# SMC_FrontPanel_ExtensionBoard_V14_5.net
KiCad netlist of a schematic drawn in EAGLE
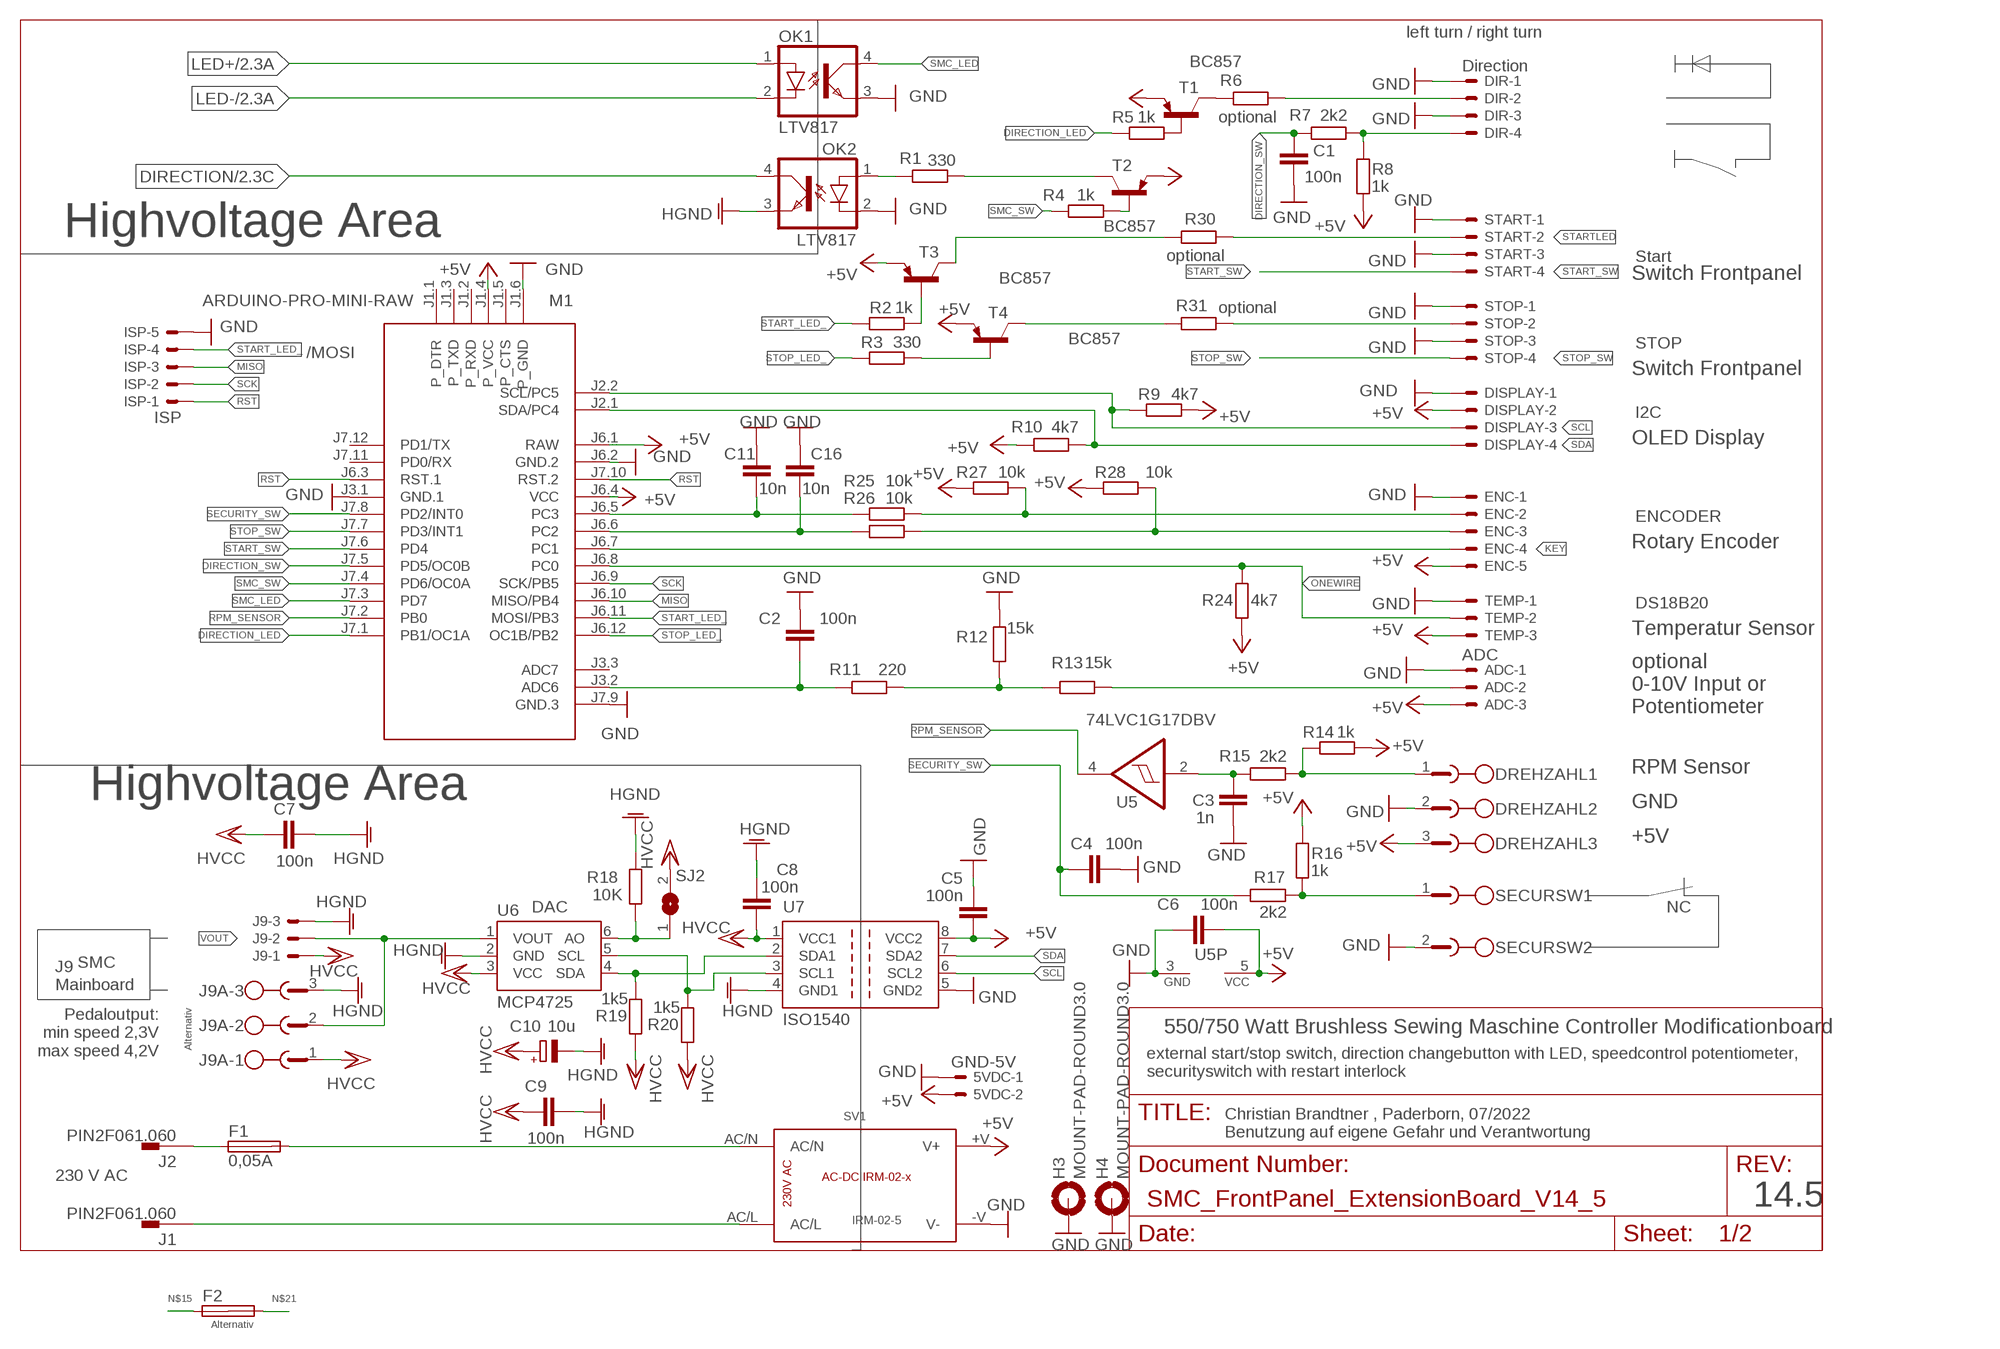
[diagram p0: schematic, sheet 1]
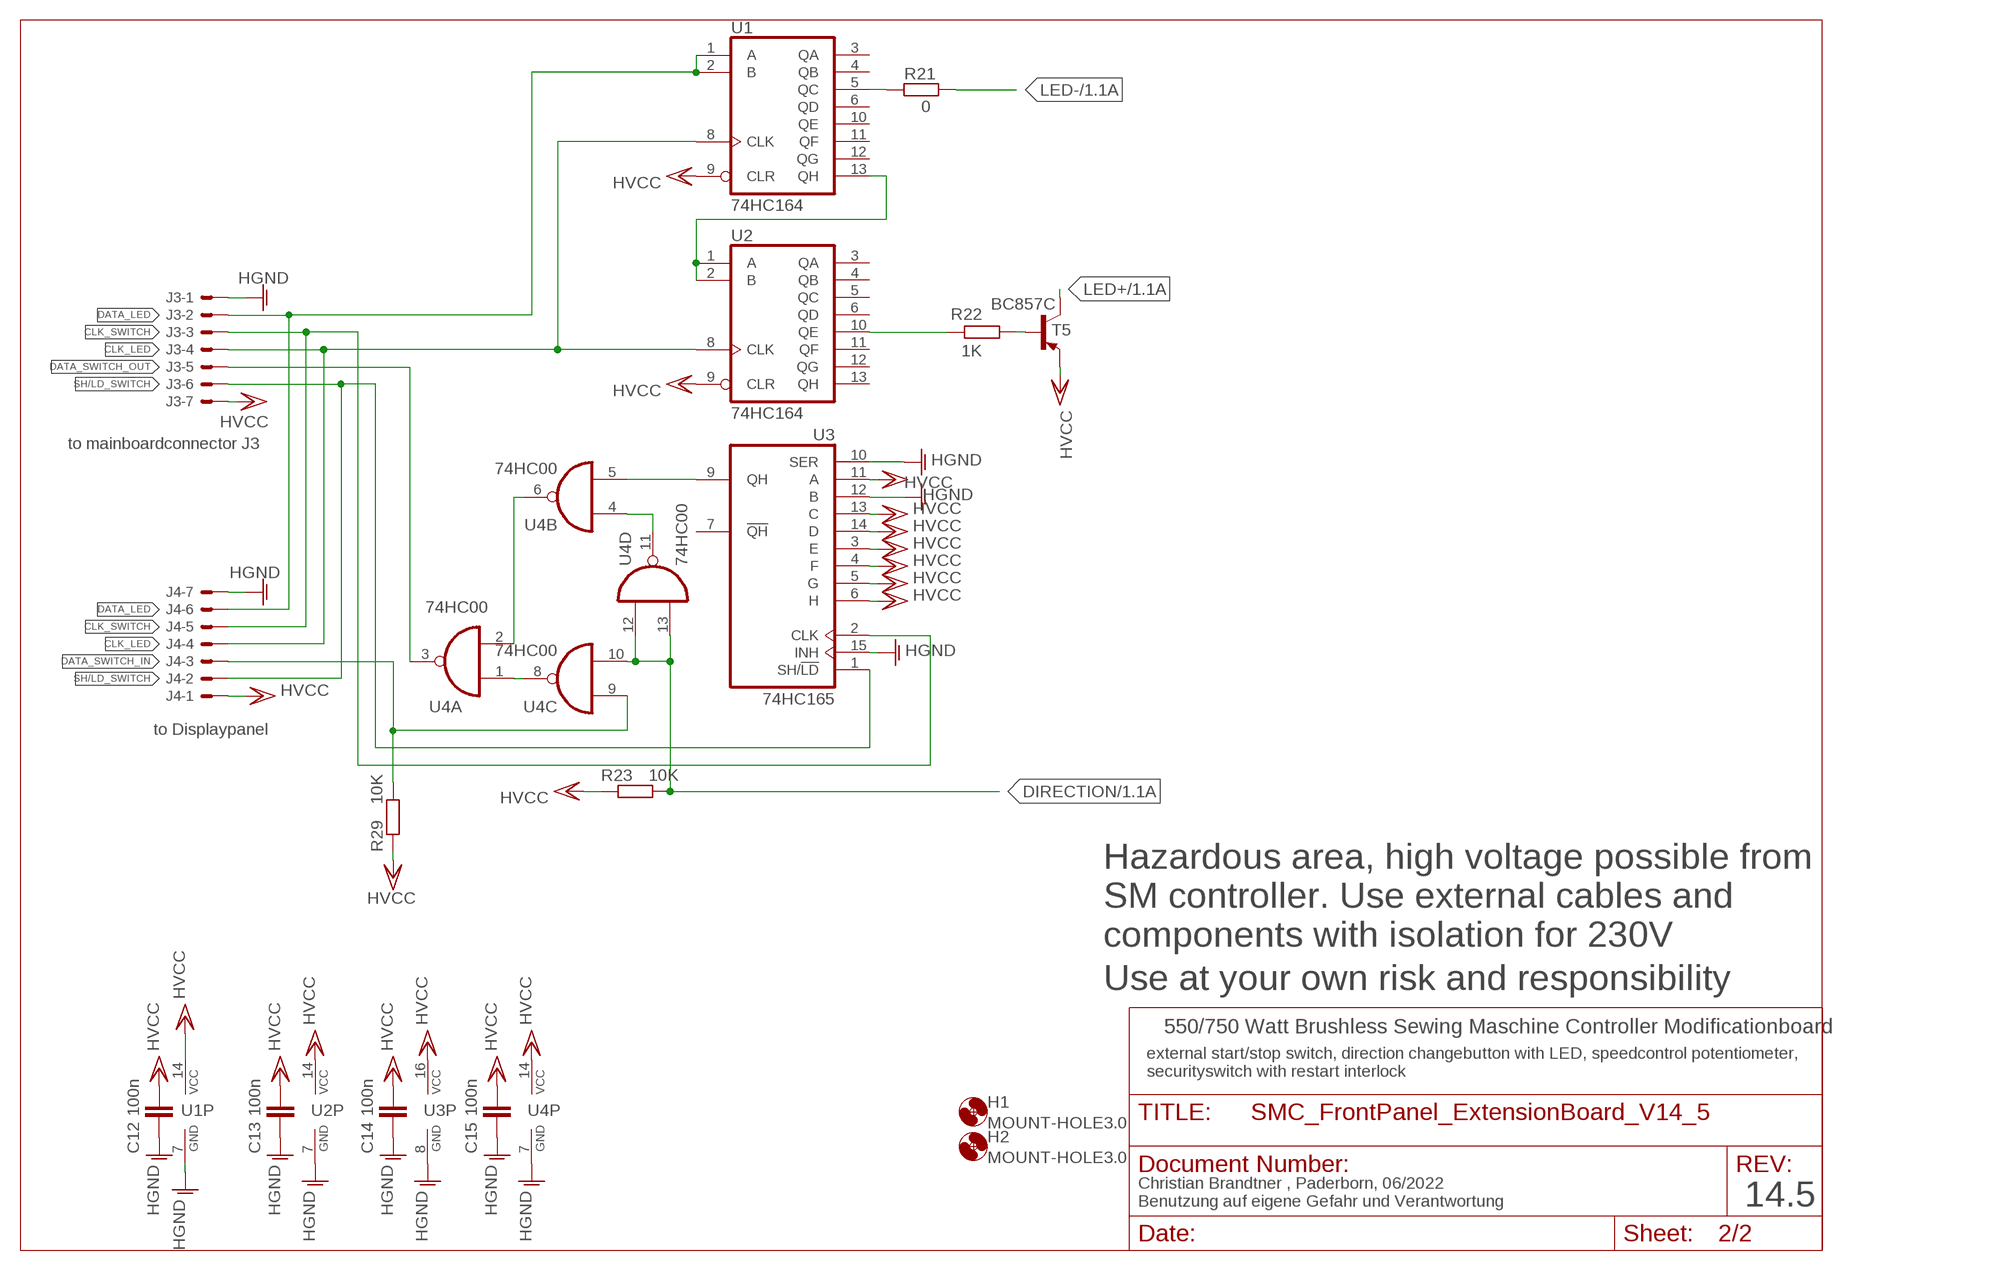
[diagram p1: schematic, sheet 2]

(export (version "E")
  (design (tool "Eeschema 10.0.6"))
  (components
    (comp (ref "5VDC")
      (value "GND-5V")
      (footprint "eagle-import:JST-XH-02-PACKAGE-ROUND-PAD")
      (libsource (lib "eagle-import") (part "JST-XH-02-PIN-ROUND-PAD"))
    )
    (comp (ref "ADC")
      (value "ADC")
      (footprint "eagle-import:JST-XH-03-PACKAGE-ROUND-PAD")
      (libsource (lib "eagle-import") (part "JST-XH-03-PIN-ROUND-PAD"))
    )
    (comp (ref "C1")
      (value "100n")
      (footprint "eagle-import:C0805")
      (libsource (lib "eagle-import") (part "C-EUC0805"))
    )
    (comp (ref "C2")
      (value "100n")
      (footprint "eagle-import:C0805")
      (libsource (lib "eagle-import") (part "C-EUC0805"))
    )
    (comp (ref "C3")
      (value "1n")
      (footprint "eagle-import:C0805")
      (libsource (lib "eagle-import") (part "C-EUC0805"))
    )
    (comp (ref "C4")
      (value "100n")
      (footprint "eagle-import:C0805")
      (libsource (lib "eagle-import") (part "C-EUC0805"))
    )
    (comp (ref "C5")
      (value "100n")
      (footprint "eagle-import:C0805")
      (libsource (lib "eagle-import") (part "C-EUC0805"))
    )
    (comp (ref "C6")
      (value "100n")
      (footprint "eagle-import:C0805")
      (libsource (lib "eagle-import") (part "C-EUC0805"))
    )
    (comp (ref "C7")
      (value "100n")
      (footprint "eagle-import:C0805")
      (libsource (lib "eagle-import") (part "C-EUC0805"))
    )
    (comp (ref "C8")
      (value "100n")
      (footprint "eagle-import:C0805")
      (libsource (lib "eagle-import") (part "C-EUC0805"))
    )
    (comp (ref "C9")
      (value "100n")
      (footprint "eagle-import:C0805")
      (libsource (lib "eagle-import") (part "C-EUC0805"))
    )
    (comp (ref "C10")
      (value "10u")
      (footprint "eagle-import:153CLV-0405")
      (libsource (lib "eagle-import") (part "CPOL-EU153CLV-0405"))
    )
    (comp (ref "C11")
      (value "10n")
      (footprint "eagle-import:C0805")
      (libsource (lib "eagle-import") (part "C-EUC0805"))
    )
    (comp (ref "C16")
      (value "10n")
      (footprint "eagle-import:C0805")
      (libsource (lib "eagle-import") (part "C-EUC0805"))
    )
    (comp (ref "DIR")
      (value "Direction")
      (footprint "eagle-import:JST-XH-04-PACKAGE-ROUND-PAD")
      (libsource (lib "eagle-import") (part "JST-XH-04-PIN-ROUND-PAD"))
    )
    (comp (ref "DISPLAY")
      (value "I2C")
      (footprint "eagle-import:JST-XH-04-PACKAGE-ROUND-PAD")
      (libsource (lib "eagle-import") (part "JST-XH-04-PIN-ROUND-PAD"))
    )
    (comp (ref "DREHZAHL")
      (value "MCV_1.5/3/-G-3.5")
      (footprint "eagle-import:1843619")
      (libsource (lib "eagle-import") (part "MCV_1.5/3/-G-3.5"))
    )
    (comp (ref "ENC")
      (value "ENCODER")
      (footprint "eagle-import:JST-XH-05-PACKAGE-ROUND-PAD")
      (libsource (lib "eagle-import") (part "JST-XH-05-PIN-ROUND-PAD"))
    )
    (comp (ref "F1")
      (value "0,05A")
      (footprint "eagle-import:MTA501100")
      (libsource (lib "eagle-import") (part "FUSE"))
    )
    (comp (ref "F2")
      (value "SHK20L")
      (footprint "eagle-import:SHK20L")
      (libsource (lib "eagle-import") (part "SHK20L"))
    )
    (comp (ref "H3")
      (value "MOUNT-PAD-ROUND3.0")
      (footprint "eagle-import:3,0-PAD")
      (libsource (lib "eagle-import") (part "MOUNT-PAD-ROUND3.0"))
    )
    (comp (ref "H4")
      (value "MOUNT-PAD-ROUND3.0")
      (footprint "eagle-import:3,0-PAD")
      (libsource (lib "eagle-import") (part "MOUNT-PAD-ROUND3.0"))
    )
    (comp (ref "ISP")
      (value "ISP")
      (footprint "eagle-import:JST-XH-05-PACKAGE-ROUND-PAD")
      (libsource (lib "eagle-import") (part "JST-XH-05-PIN-ROUND-PAD"))
    )
    (comp (ref "J1")
      (value "PIN2F061.060")
      (footprint "eagle-import:F061.060")
      (libsource (lib "eagle-import") (part "PIN2F061.060"))
    )
    (comp (ref "J2")
      (value "PIN2F061.060")
      (footprint "eagle-import:F061.060")
      (libsource (lib "eagle-import") (part "PIN2F061.060"))
    )
    (comp (ref "J9")
      (value "JST-XH-03-PIN-ROUND-PAD")
      (footprint "eagle-import:JST-XH-03-PACKAGE-ROUND-PAD")
      (libsource (lib "eagle-import") (part "JST-XH-03-PIN-ROUND-PAD"))
    )
    (comp (ref "J9A-")
      (value "MCV_1.5/3/-G-3.5")
      (footprint "eagle-import:1843619")
      (libsource (lib "eagle-import") (part "MCV_1.5/3/-G-3.5"))
    )
    (comp (ref "M1")
      (value "ARDUINO-PRO-MINI-RAW")
      (footprint "eagle-import:ARDUINO-PRO-MINI")
      (libsource (lib "eagle-import") (part "ARDUINO-PRO-MINI-RAW"))
    )
    (comp (ref "OK1")
      (value "LTV817")
      (footprint "eagle-import:SMD4-7")
      (fields (field (name "MF") "VISHAY/TELEFUNKEN") (field (name "MPN") "SFH6186-2"))
      (libsource (lib "eagle-import") (part "SFH618?6-2"))
    )
    (comp (ref "OK2")
      (value "LTV817")
      (footprint "eagle-import:SMD4-7")
      (fields (field (name "MF") "VISHAY/TELEFUNKEN") (field (name "MPN") "SFH6186-2"))
      (libsource (lib "eagle-import") (part "SFH618?6-2"))
    )
    (comp (ref "R1")
      (value "330")
      (footprint "eagle-import:R0805")
      (libsource (lib "eagle-import") (part "R-EU_R0805"))
    )
    (comp (ref "R2")
      (value "1k")
      (footprint "eagle-import:R0805")
      (libsource (lib "eagle-import") (part "R-EU_R0805"))
    )
    (comp (ref "R3")
      (value "330")
      (footprint "eagle-import:R0805")
      (libsource (lib "eagle-import") (part "R-EU_R0805"))
    )
    (comp (ref "R4")
      (value "1k")
      (footprint "eagle-import:R0805")
      (libsource (lib "eagle-import") (part "R-EU_R0805"))
    )
    (comp (ref "R5")
      (value "1k")
      (footprint "eagle-import:R0805")
      (libsource (lib "eagle-import") (part "R-EU_R0805"))
    )
    (comp (ref "R6")
      (value "optional")
      (footprint "eagle-import:R0805")
      (libsource (lib "eagle-import") (part "R-EU_R0805"))
    )
    (comp (ref "R7")
      (value "2k2")
      (footprint "eagle-import:R0805")
      (libsource (lib "eagle-import") (part "R-EU_R0805"))
    )
    (comp (ref "R8")
      (value "1k")
      (footprint "eagle-import:R0805")
      (libsource (lib "eagle-import") (part "R-EU_R0805"))
    )
    (comp (ref "R9")
      (value "4k7")
      (footprint "eagle-import:R0805")
      (libsource (lib "eagle-import") (part "R-EU_R0805"))
    )
    (comp (ref "R10")
      (value "4k7")
      (footprint "eagle-import:R0805")
      (libsource (lib "eagle-import") (part "R-EU_R0805"))
    )
    (comp (ref "R11")
      (value "220")
      (footprint "eagle-import:R0805")
      (libsource (lib "eagle-import") (part "R-EU_R0805"))
    )
    (comp (ref "R12")
      (value "15k")
      (footprint "eagle-import:R0805")
      (libsource (lib "eagle-import") (part "R-EU_R0805"))
    )
    (comp (ref "R13")
      (value "15k")
      (footprint "eagle-import:R0805")
      (libsource (lib "eagle-import") (part "R-EU_R0805"))
    )
    (comp (ref "R14")
      (value "1k")
      (footprint "eagle-import:R0805")
      (libsource (lib "eagle-import") (part "R-EU_R0805"))
    )
    (comp (ref "R15")
      (value "2k2")
      (footprint "eagle-import:R0805")
      (libsource (lib "eagle-import") (part "R-EU_R0805"))
    )
    (comp (ref "R16")
      (value "1k")
      (footprint "eagle-import:R0805")
      (libsource (lib "eagle-import") (part "R-EU_R0805"))
    )
    (comp (ref "R17")
      (value "2k2")
      (footprint "eagle-import:R0805")
      (libsource (lib "eagle-import") (part "R-EU_R0805"))
    )
    (comp (ref "R18")
      (value "10K")
      (footprint "eagle-import:R0805")
      (libsource (lib "eagle-import") (part "R-EU_R0805"))
    )
    (comp (ref "R19")
      (value "1k5")
      (footprint "eagle-import:R0805")
      (libsource (lib "eagle-import") (part "R-EU_R0805"))
    )
    (comp (ref "R20")
      (value "1k5")
      (footprint "eagle-import:R0805")
      (libsource (lib "eagle-import") (part "R-EU_R0805"))
    )
    (comp (ref "R24")
      (value "4k7")
      (footprint "eagle-import:R0805")
      (libsource (lib "eagle-import") (part "R-EU_R0805"))
    )
    (comp (ref "R25")
      (value "10k")
      (footprint "eagle-import:R0805")
      (libsource (lib "eagle-import") (part "R-EU_R0805"))
    )
    (comp (ref "R26")
      (value "10k")
      (footprint "eagle-import:R0805")
      (libsource (lib "eagle-import") (part "R-EU_R0805"))
    )
    (comp (ref "R27")
      (value "10k")
      (footprint "eagle-import:R0805")
      (libsource (lib "eagle-import") (part "R-EU_R0805"))
    )
    (comp (ref "R28")
      (value "10k")
      (footprint "eagle-import:R0805")
      (libsource (lib "eagle-import") (part "R-EU_R0805"))
    )
    (comp (ref "R30")
      (value "optional")
      (footprint "eagle-import:R0805")
      (libsource (lib "eagle-import") (part "R-EU_R0805"))
    )
    (comp (ref "R31")
      (value "optional")
      (footprint "eagle-import:R0805")
      (libsource (lib "eagle-import") (part "R-EU_R0805"))
    )
    (comp (ref "SECURSW")
      (value "MCV_1,5/2-G-3,5")
      (footprint "eagle-import:1843606")
      (libsource (lib "eagle-import") (part "MCV_1,5/2-G-3,5"))
    )
    (comp (ref "SJ2") (value "SJ") (footprint "eagle-import:SJ") (libsource (lib "eagle-import") (part "SJ")))
    (comp (ref "START")
      (value "Start")
      (footprint "eagle-import:JST-XH-04-PACKAGE-ROUND-PAD")
      (libsource (lib "eagle-import") (part "JST-XH-04-PIN-ROUND-PAD"))
    )
    (comp (ref "STOP")
      (value "STOP")
      (footprint "eagle-import:JST-XH-04-PACKAGE-ROUND-PAD")
      (libsource (lib "eagle-import") (part "JST-XH-04-PIN-ROUND-PAD"))
    )
    (comp (ref "SV1")
      (value "IRM-02-5")
      (footprint "eagle-import:IRM-02-X")
      (libsource (lib "eagle-import") (part "IRM-02-X"))
    )
    (comp (ref "T1")
      (value "BC857")
      (footprint "eagle-import:SOT23-BEC")
      (libsource (lib "eagle-import") (part "BC857SMDA"))
    )
    (comp (ref "T2")
      (value "BC857")
      (footprint "eagle-import:SOT23-BEC")
      (libsource (lib "eagle-import") (part "BC857SMDA"))
    )
    (comp (ref "T3")
      (value "BC857")
      (footprint "eagle-import:SOT23-BEC")
      (libsource (lib "eagle-import") (part "BC857SMDA"))
    )
    (comp (ref "T4")
      (value "BC857")
      (footprint "eagle-import:SOT23-BEC")
      (libsource (lib "eagle-import") (part "BC857SMDA"))
    )
    (comp (ref "TEMP")
      (value "DS18B20")
      (footprint "eagle-import:JST-XH-03-PACKAGE-ROUND-PAD")
      (libsource (lib "eagle-import") (part "JST-XH-03-PIN-ROUND-PAD"))
    )
    (comp (ref "U5")
      (value "74LVC1G17DBV")
      (footprint "eagle-import:SOT23-5")
      (libsource (lib "eagle-import") (part "741G17DBVLVC"))
    )
    (comp (ref "U6")
      (value "MCP4725")
      (footprint "eagle-import:SOT23-6")
      (libsource (lib "eagle-import") (part "MCP4725SOT-23"))
    )
    (comp (ref "U7")
      (value "ISO1540")
      (footprint "eagle-import:SO-08")
      (libsource (lib "eagle-import") (part "ISO1540"))
    )
    (comp (ref "C12")
      (value "100n")
      (footprint "eagle-import:C0805")
      (libsource (lib "eagle-import") (part "C-EUC0805"))
    )
    (comp (ref "C13")
      (value "100n")
      (footprint "eagle-import:C0805")
      (libsource (lib "eagle-import") (part "C-EUC0805"))
    )
    (comp (ref "C14")
      (value "100n")
      (footprint "eagle-import:C0805")
      (libsource (lib "eagle-import") (part "C-EUC0805"))
    )
    (comp (ref "C15")
      (value "100n")
      (footprint "eagle-import:C0805")
      (libsource (lib "eagle-import") (part "C-EUC0805"))
    )
    (comp (ref "H1")
      (value "MOUNT-HOLE3.0")
      (footprint "eagle-import:3,0")
      (libsource (lib "eagle-import") (part "MOUNT-HOLE3.0"))
    )
    (comp (ref "H2")
      (value "MOUNT-HOLE3.0")
      (footprint "eagle-import:3,0")
      (libsource (lib "eagle-import") (part "MOUNT-HOLE3.0"))
    )
    (comp (ref "J3")
      (value "to mainboardconnector J3")
      (footprint "eagle-import:JST-XH-07-PACKAGE-ROUND-PAD")
      (libsource (lib "eagle-import") (part "JST-XH-07-PIN-ROUND-PAD"))
    )
    (comp (ref "J4")
      (value "to Displaypanel")
      (footprint "eagle-import:JST-XH-07-PACKAGE-ROUND-PAD")
      (libsource (lib "eagle-import") (part "JST-XH-07-PIN-ROUND-PAD"))
    )
    (comp (ref "R21")
      (value "0")
      (footprint "eagle-import:R0805")
      (libsource (lib "eagle-import") (part "R-EU_R0805"))
    )
    (comp (ref "R22")
      (value "1K")
      (footprint "eagle-import:R0805")
      (libsource (lib "eagle-import") (part "R-EU_R0805"))
    )
    (comp (ref "R23")
      (value "10K")
      (footprint "eagle-import:R0805")
      (libsource (lib "eagle-import") (part "R-EU_R0805"))
    )
    (comp (ref "R29")
      (value "10K")
      (footprint "eagle-import:R0805")
      (libsource (lib "eagle-import") (part "R-EU_R0805"))
    )
    (comp (ref "T5")
      (value "BC857C")
      (footprint "eagle-import:SOT23-BEC")
      (libsource (lib "eagle-import") (part "-PNP-SOT23-BECBC857C"))
    )
    (comp (ref "U1")
      (value "74HC164")
      (footprint "eagle-import:SO14")
      (libsource (lib "eagle-import") (part "74164DHC"))
    )
    (comp (ref "U2")
      (value "74HC164")
      (footprint "eagle-import:SO14")
      (libsource (lib "eagle-import") (part "74164DHC"))
    )
    (comp (ref "U3")
      (value "74HC165")
      (footprint "eagle-import:SO16")
      (libsource (lib "eagle-import") (part "74165DHC"))
    )
    (comp (ref "U4")
      (value "74HC00")
      (footprint "eagle-import:SO14")
      (libsource (lib "eagle-import") (part "7400DHC"))
    )
  )
  (nets
    (net (code "1") (name "+5V") (class "Default")
      (node (ref "5VDC") (pin "2") (pinfunction "S_2") (pintype "passive"))
      (node (ref "ADC") (pin "3") (pinfunction "S_3") (pintype "passive"))
      (node (ref "C5") (pin "1") (pinfunction "1_1") (pintype "passive"))
      (node (ref "C6") (pin "1") (pinfunction "1_1") (pintype "passive"))
      (node (ref "DISPLAY") (pin "2") (pinfunction "S_2") (pintype "passive"))
      (node (ref "DREHZAHL") (pin "3") (pinfunction "1_3") (pintype "passive"))
      (node (ref "ENC") (pin "5") (pinfunction "S_5") (pintype "passive"))
      (node (ref "M1") (pin "J1.4") (pinfunction "P_VCC_J1.4") (pintype "bidirectional"))
      (node (ref "M1") (pin "J6.1") (pinfunction "RAW_J6.1") (pintype "power_in"))
      (node (ref "M1") (pin "J6.4") (pinfunction "VCC_J6.4") (pintype "power_in"))
      (node (ref "R10") (pin "1") (pinfunction "1_1") (pintype "passive"))
      (node (ref "R14") (pin "1") (pinfunction "1_1") (pintype "passive"))
      (node (ref "R16") (pin "1") (pinfunction "1_1") (pintype "passive"))
      (node (ref "R24") (pin "2") (pinfunction "2_2") (pintype "passive"))
      (node (ref "R27") (pin "1") (pinfunction "1_1") (pintype "passive"))
      (node (ref "R28") (pin "1") (pinfunction "1_1") (pintype "passive"))
      (node (ref "R8") (pin "2") (pinfunction "2_2") (pintype "passive"))
      (node (ref "R9") (pin "1") (pinfunction "1_1") (pintype "passive"))
      (node (ref "SV1") (pin "+V") (pinfunction "V+_+V") (pintype "bidirectional"))
      (node (ref "T1") (pin "E") (pinfunction "E_E") (pintype "passive"))
      (node (ref "T2") (pin "E") (pinfunction "E_E") (pintype "passive"))
      (node (ref "T3") (pin "E") (pinfunction "E_E") (pintype "passive"))
      (node (ref "T4") (pin "E") (pinfunction "E_E") (pintype "passive"))
      (node (ref "TEMP") (pin "3") (pinfunction "S_3") (pintype "passive"))
      (node (ref "U5") (pin "5") (pinfunction "VCC_5") (pintype "power_in"))
      (node (ref "U7") (pin "8") (pinfunction "VCC2_8") (pintype "power_in"))
    )
    (net (code "2") (name "CLK_LED") (class "Default")
      (node (ref "J3") (pin "4") (pinfunction "S_4") (pintype "passive"))
      (node (ref "J4") (pin "4") (pinfunction "S_4") (pintype "passive"))
      (node (ref "U1") (pin "8") (pinfunction "CLK_8") (pintype "input"))
      (node (ref "U2") (pin "8") (pinfunction "CLK_8") (pintype "input"))
    )
    (net (code "3") (name "CLK_SWITCH") (class "Default")
      (node (ref "J3") (pin "3") (pinfunction "S_3") (pintype "passive"))
      (node (ref "J4") (pin "5") (pinfunction "S_5") (pintype "passive"))
      (node (ref "U3") (pin "2") (pinfunction "CLK_2") (pintype "input"))
    )
    (net (code "4") (name "DATA_LED") (class "Default")
      (node (ref "J3") (pin "2") (pinfunction "S_2") (pintype "passive"))
      (node (ref "J4") (pin "6") (pinfunction "S_6") (pintype "passive"))
      (node (ref "U1") (pin "1") (pinfunction "A_1") (pintype "input"))
      (node (ref "U1") (pin "2") (pinfunction "B_2") (pintype "input"))
    )
    (net (code "5") (name "DATA_SWITCH_IN") (class "Default")
      (node (ref "J4") (pin "3") (pinfunction "S_3") (pintype "passive"))
      (node (ref "R29") (pin "1") (pinfunction "1_1") (pintype "passive"))
      (node (ref "U4") (pin "9") (pinfunction "I0_9") (pintype "input"))
    )
    (net (code "6") (name "DATA_SWITCH_OUT") (class "Default")
      (node (ref "J3") (pin "5") (pinfunction "S_5") (pintype "passive"))
      (node (ref "U4") (pin "3") (pinfunction "O_3") (pintype "output"))
    )
    (net (code "7") (name "DIRECTION") (class "Default")
      (node (ref "OK2") (pin "4") (pinfunction "COL_4") (pintype "passive"))
      (node (ref "R23") (pin "1") (pinfunction "1_1") (pintype "passive"))
      (node (ref "U4") (pin "10") (pinfunction "I1_10") (pintype "input"))
      (node (ref "U4") (pin "12") (pinfunction "I0_12") (pintype "input"))
      (node (ref "U4") (pin "13") (pinfunction "I1_13") (pintype "input"))
    )
    (net (code "8") (name "DIRECTION_LED") (class "Default")
      (node (ref "M1") (pin "J7.1") (pinfunction "PB1/OC1A_J7.1") (pintype "bidirectional"))
      (node (ref "R5") (pin "2") (pinfunction "2_2") (pintype "passive"))
    )
    (net (code "9") (name "DIRECTION_SW") (class "Default")
      (node (ref "C1") (pin "2") (pinfunction "2_2") (pintype "passive"))
      (node (ref "M1") (pin "J7.5") (pinfunction "PD5/OC0B_J7.5") (pintype "bidirectional"))
      (node (ref "R7") (pin "1") (pinfunction "1_1") (pintype "passive"))
    )
    (net (code "10") (name "GND") (class "Default")
      (node (ref "5VDC") (pin "1") (pinfunction "S_1") (pintype "passive"))
      (node (ref "ADC") (pin "1") (pinfunction "S_1") (pintype "passive"))
      (node (ref "C1") (pin "1") (pinfunction "1_1") (pintype "passive"))
      (node (ref "C11") (pin "2") (pinfunction "2_2") (pintype "passive"))
      (node (ref "C16") (pin "2") (pinfunction "2_2") (pintype "passive"))
      (node (ref "C2") (pin "2") (pinfunction "2_2") (pintype "passive"))
      (node (ref "C3") (pin "1") (pinfunction "1_1") (pintype "passive"))
      (node (ref "C4") (pin "2") (pinfunction "2_2") (pintype "passive"))
      (node (ref "C5") (pin "2") (pinfunction "2_2") (pintype "passive"))
      (node (ref "C6") (pin "2") (pinfunction "2_2") (pintype "passive"))
      (node (ref "DIR") (pin "1") (pinfunction "S_1") (pintype "passive"))
      (node (ref "DIR") (pin "3") (pinfunction "S_3") (pintype "passive"))
      (node (ref "DISPLAY") (pin "1") (pinfunction "S_1") (pintype "passive"))
      (node (ref "DREHZAHL") (pin "2") (pinfunction "1_2") (pintype "passive"))
      (node (ref "ENC") (pin "1") (pinfunction "S_1") (pintype "passive"))
      (node (ref "H3") (pin "B3,0") (pinfunction "MOUNT_B3,0") (pintype "passive"))
      (node (ref "H4") (pin "B3,0") (pinfunction "MOUNT_B3,0") (pintype "passive"))
      (node (ref "ISP") (pin "5") (pinfunction "S_5") (pintype "passive"))
      (node (ref "M1") (pin "J1.6") (pinfunction "P_GND_J1.6") (pintype "bidirectional"))
      (node (ref "M1") (pin "J3.1") (pinfunction "GND.1_J3.1") (pintype "power_in"))
      (node (ref "M1") (pin "J6.2") (pinfunction "GND.2_J6.2") (pintype "power_in"))
      (node (ref "M1") (pin "J7.9") (pinfunction "GND.3_J7.9") (pintype "bidirectional"))
      (node (ref "OK1") (pin "3") (pinfunction "EMIT_3") (pintype "passive"))
      (node (ref "OK2") (pin "2") (pinfunction "C_2") (pintype "passive"))
      (node (ref "R12") (pin "2") (pinfunction "2_2") (pintype "passive"))
      (node (ref "SECURSW") (pin "2") (pinfunction "1_2") (pintype "passive"))
      (node (ref "START") (pin "1") (pinfunction "S_1") (pintype "passive"))
      (node (ref "START") (pin "3") (pinfunction "S_3") (pintype "passive"))
      (node (ref "STOP") (pin "1") (pinfunction "S_1") (pintype "passive"))
      (node (ref "STOP") (pin "3") (pinfunction "S_3") (pintype "passive"))
      (node (ref "SV1") (pin "-V") (pinfunction "V-_-V") (pintype "bidirectional"))
      (node (ref "TEMP") (pin "1") (pinfunction "S_1") (pintype "passive"))
      (node (ref "U5") (pin "3") (pinfunction "GND_3") (pintype "power_in"))
      (node (ref "U7") (pin "5") (pinfunction "GND2_5") (pintype "power_in"))
    )
    (net (code "11") (name "HGND") (class "Default")
      (node (ref "C10") (pin "-") (pinfunction "-_-") (pintype "passive"))
      (node (ref "C12") (pin "1") (pinfunction "1_1") (pintype "passive"))
      (node (ref "C13") (pin "1") (pinfunction "1_1") (pintype "passive"))
      (node (ref "C14") (pin "1") (pinfunction "1_1") (pintype "passive"))
      (node (ref "C15") (pin "1") (pinfunction "1_1") (pintype "passive"))
      (node (ref "C7") (pin "1") (pinfunction "1_1") (pintype "passive"))
      (node (ref "C8") (pin "2") (pinfunction "2_2") (pintype "passive"))
      (node (ref "C9") (pin "1") (pinfunction "1_1") (pintype "passive"))
      (node (ref "J3") (pin "1") (pinfunction "S_1") (pintype "passive"))
      (node (ref "J4") (pin "7") (pinfunction "S_7") (pintype "passive"))
      (node (ref "J9") (pin "3") (pinfunction "S_3") (pintype "passive"))
      (node (ref "J9A-") (pin "3") (pinfunction "1_3") (pintype "passive"))
      (node (ref "OK2") (pin "3") (pinfunction "EMIT_3") (pintype "passive"))
      (node (ref "R18") (pin "1") (pinfunction "1_1") (pintype "passive"))
      (node (ref "U1") (pin "7") (pinfunction "GND_7") (pintype "power_in"))
      (node (ref "U2") (pin "7") (pinfunction "GND_7") (pintype "power_in"))
      (node (ref "U3") (pin "10") (pinfunction "SER_10") (pintype "input"))
      (node (ref "U3") (pin "12") (pinfunction "B_12") (pintype "input"))
      (node (ref "U3") (pin "15") (pinfunction "INH_15") (pintype "input"))
      (node (ref "U3") (pin "8") (pinfunction "GND_8") (pintype "power_in"))
      (node (ref "U4") (pin "7") (pinfunction "GND_7") (pintype "power_in"))
      (node (ref "U6") (pin "2") (pinfunction "GND_2") (pintype "bidirectional"))
      (node (ref "U7") (pin "4") (pinfunction "GND1_4") (pintype "power_in"))
    )
    (net (code "12") (name "HVCC") (class "Default")
      (node (ref "C10") (pin "+") (pinfunction "+_+") (pintype "passive"))
      (node (ref "C12") (pin "2") (pinfunction "2_2") (pintype "passive"))
      (node (ref "C13") (pin "2") (pinfunction "2_2") (pintype "passive"))
      (node (ref "C14") (pin "2") (pinfunction "2_2") (pintype "passive"))
      (node (ref "C15") (pin "2") (pinfunction "2_2") (pintype "passive"))
      (node (ref "C7") (pin "2") (pinfunction "2_2") (pintype "passive"))
      (node (ref "C8") (pin "1") (pinfunction "1_1") (pintype "passive"))
      (node (ref "C9") (pin "2") (pinfunction "2_2") (pintype "passive"))
      (node (ref "J3") (pin "7") (pinfunction "S_7") (pintype "passive"))
      (node (ref "J4") (pin "1") (pinfunction "S_1") (pintype "passive"))
      (node (ref "J9") (pin "1") (pinfunction "S_1") (pintype "passive"))
      (node (ref "J9A-") (pin "1") (pinfunction "1_1") (pintype "passive"))
      (node (ref "R19") (pin "2") (pinfunction "2_2") (pintype "passive"))
      (node (ref "R20") (pin "2") (pinfunction "2_2") (pintype "passive"))
      (node (ref "R23") (pin "2") (pinfunction "2_2") (pintype "passive"))
      (node (ref "R29") (pin "2") (pinfunction "2_2") (pintype "passive"))
      (node (ref "SJ2") (pin "2") (pinfunction "2_2") (pintype "passive"))
      (node (ref "T5") (pin "E") (pinfunction "E_E") (pintype "passive"))
      (node (ref "U1") (pin "14") (pinfunction "VCC_14") (pintype "power_in"))
      (node (ref "U1") (pin "9") (pinfunction "CLR_9") (pintype "input"))
      (node (ref "U2") (pin "14") (pinfunction "VCC_14") (pintype "power_in"))
      (node (ref "U2") (pin "9") (pinfunction "CLR_9") (pintype "input"))
      (node (ref "U3") (pin "11") (pinfunction "A_11") (pintype "input"))
      (node (ref "U3") (pin "13") (pinfunction "C_13") (pintype "input"))
      (node (ref "U3") (pin "14") (pinfunction "D_14") (pintype "input"))
      (node (ref "U3") (pin "16") (pinfunction "VCC_16") (pintype "power_in"))
      (node (ref "U3") (pin "3") (pinfunction "E_3") (pintype "input"))
      (node (ref "U3") (pin "4") (pinfunction "F_4") (pintype "input"))
      (node (ref "U3") (pin "5") (pinfunction "G_5") (pintype "input"))
      (node (ref "U3") (pin "6") (pinfunction "H_6") (pintype "input"))
      (node (ref "U4") (pin "14") (pinfunction "VCC_14") (pintype "power_in"))
      (node (ref "U6") (pin "3") (pinfunction "VCC_3") (pintype "bidirectional"))
      (node (ref "U7") (pin "1") (pinfunction "VCC1_1") (pintype "power_in"))
    )
    (net (code "13") (name "KEY") (class "Default")
      (node (ref "ENC") (pin "4") (pinfunction "S_4") (pintype "passive"))
      (node (ref "M1") (pin "J6.7") (pinfunction "PC1_J6.7") (pintype "bidirectional"))
    )
    (net (code "14") (name "LED+") (class "Default")
      (node (ref "OK1") (pin "1") (pinfunction "A_1") (pintype "passive"))
      (node (ref "T5") (pin "C") (pinfunction "C_C") (pintype "passive"))
    )
    (net (code "15") (name "LED-") (class "Default")
      (node (ref "OK1") (pin "2") (pinfunction "C_2") (pintype "passive"))
      (node (ref "R21") (pin "2") (pinfunction "2_2") (pintype "passive"))
    )
    (net (code "16") (name "MISO") (class "Default")
      (node (ref "ISP") (pin "3") (pinfunction "S_3") (pintype "passive"))
      (node (ref "M1") (pin "J6.10") (pinfunction "MISO/PB4_J6.10") (pintype "bidirectional"))
    )
    (net (code "17") (name "N$15") (class "Default")
      (node (ref "F1") (pin "1") (pinfunction "1_1") (pintype "passive"))
      (node (ref "F2") (pin "1A") (pinfunction "1A_1A") (pintype "passive"))
      (node (ref "J2") (pin "A1") (pinfunction "1_A1") (pintype "passive"))
      (node (ref "J2") (pin "A2") (pinfunction "1_A2") (pintype "passive"))
    )
    (net (code "18") (name "N$21") (class "Default")
      (node (ref "F1") (pin "2") (pinfunction "2_2") (pintype "passive"))
      (node (ref "F2") (pin "2A") (pinfunction "2A_2A") (pintype "passive"))
      (node (ref "SV1") (pin "AC/N") (pinfunction "AC/N_AC/N") (pintype "bidirectional"))
    )
    (net (code "19") (name "Net-(ADCB-S)") (class "Default")
      (node (ref "ADC") (pin "2") (pinfunction "S_2") (pintype "passive"))
      (node (ref "R13") (pin "1") (pinfunction "1_1") (pintype "passive"))
    )
    (net (code "20") (name "Net-(DIRB-S)") (class "Default")
      (node (ref "DIR") (pin "2") (pinfunction "S_2") (pintype "passive"))
      (node (ref "R6") (pin "1") (pinfunction "1_1") (pintype "passive"))
    )
    (net (code "21") (name "Net-(DIRD-S)") (class "Default")
      (node (ref "DIR") (pin "4") (pinfunction "S_4") (pintype "passive"))
      (node (ref "R7") (pin "2") (pinfunction "2_2") (pintype "passive"))
      (node (ref "R8") (pin "1") (pinfunction "1_1") (pintype "passive"))
    )
    (net (code "22") (name "Net-(DREHZAHL-Pad1)") (class "Default")
      (node (ref "DREHZAHL") (pin "1") (pinfunction "1_1") (pintype "passive"))
      (node (ref "R14") (pin "2") (pinfunction "2_2") (pintype "passive"))
      (node (ref "R15") (pin "2") (pinfunction "2_2") (pintype "passive"))
    )
    (net (code "23") (name "Net-(ENCB-S)") (class "Default")
      (node (ref "ENC") (pin "2") (pinfunction "S_2") (pintype "passive"))
      (node (ref "R25") (pin "2") (pinfunction "2_2") (pintype "passive"))
      (node (ref "R27") (pin "2") (pinfunction "2_2") (pintype "passive"))
    )
    (net (code "24") (name "Net-(ENCC-S)") (class "Default")
      (node (ref "ENC") (pin "3") (pinfunction "S_3") (pintype "passive"))
      (node (ref "R26") (pin "2") (pinfunction "2_2") (pintype "passive"))
      (node (ref "R28") (pin "2") (pinfunction "2_2") (pintype "passive"))
    )
    (net (code "25") (name "Net-(J1-1-PadA1)") (class "Default")
      (node (ref "J1") (pin "A1") (pinfunction "1_A1") (pintype "passive"))
      (node (ref "J1") (pin "A2") (pinfunction "1_A2") (pintype "passive"))
      (node (ref "SV1") (pin "AC/L") (pinfunction "AC/L_AC/L") (pintype "bidirectional"))
    )
    (net (code "26") (name "Net-(M1-ADC6)") (class "Default")
      (node (ref "C2") (pin "1") (pinfunction "1_1") (pintype "passive"))
      (node (ref "M1") (pin "J3.2") (pinfunction "ADC6_J3.2") (pintype "bidirectional"))
      (node (ref "R11") (pin "1") (pinfunction "1_1") (pintype "passive"))
    )
    (net (code "27") (name "Net-(M1-PC2)") (class "Default")
      (node (ref "C16") (pin "1") (pinfunction "1_1") (pintype "passive"))
      (node (ref "M1") (pin "J6.6") (pinfunction "PC2_J6.6") (pintype "bidirectional"))
      (node (ref "R26") (pin "1") (pinfunction "1_1") (pintype "passive"))
    )
    (net (code "28") (name "Net-(M1-PC3)") (class "Default")
      (node (ref "C11") (pin "1") (pinfunction "1_1") (pintype "passive"))
      (node (ref "M1") (pin "J6.5") (pinfunction "PC3_J6.5") (pintype "bidirectional"))
      (node (ref "R25") (pin "1") (pinfunction "1_1") (pintype "passive"))
    )
    (net (code "29") (name "Net-(OK2-A)") (class "Default")
      (node (ref "OK2") (pin "1") (pinfunction "A_1") (pintype "passive"))
      (node (ref "R1") (pin "2") (pinfunction "2_2") (pintype "passive"))
    )
    (net (code "30") (name "Net-(R1-Pad1)") (class "Default")
      (node (ref "R1") (pin "1") (pinfunction "1_1") (pintype "passive"))
      (node (ref "T2") (pin "C") (pinfunction "C_C") (pintype "passive"))
    )
    (net (code "31") (name "Net-(R2-Pad1)") (class "Default")
      (node (ref "R2") (pin "1") (pinfunction "1_1") (pintype "passive"))
      (node (ref "T3") (pin "B") (pinfunction "B_B") (pintype "passive"))
    )
    (net (code "32") (name "Net-(R3-Pad1)") (class "Default")
      (node (ref "R3") (pin "1") (pinfunction "1_1") (pintype "passive"))
      (node (ref "T4") (pin "B") (pinfunction "B_B") (pintype "passive"))
    )
    (net (code "33") (name "Net-(R4-Pad1)") (class "Default")
      (node (ref "R4") (pin "1") (pinfunction "1_1") (pintype "passive"))
      (node (ref "T2") (pin "B") (pinfunction "B_B") (pintype "passive"))
    )
    (net (code "34") (name "Net-(R5-Pad1)") (class "Default")
      (node (ref "R5") (pin "1") (pinfunction "1_1") (pintype "passive"))
      (node (ref "T1") (pin "B") (pinfunction "B_B") (pintype "passive"))
    )
    (net (code "35") (name "Net-(R6-Pad2)") (class "Default")
      (node (ref "R6") (pin "2") (pinfunction "2_2") (pintype "passive"))
      (node (ref "T1") (pin "C") (pinfunction "C_C") (pintype "passive"))
    )
    (net (code "36") (name "Net-(R11-Pad2)") (class "Default")
      (node (ref "R11") (pin "2") (pinfunction "2_2") (pintype "passive"))
      (node (ref "R12") (pin "1") (pinfunction "1_1") (pintype "passive"))
      (node (ref "R13") (pin "2") (pinfunction "2_2") (pintype "passive"))
    )
    (net (code "37") (name "Net-(R16-Pad2)") (class "Default")
      (node (ref "R16") (pin "2") (pinfunction "2_2") (pintype "passive"))
      (node (ref "R17") (pin "2") (pinfunction "2_2") (pintype "passive"))
      (node (ref "SECURSW") (pin "1") (pinfunction "1_1") (pintype "passive"))
    )
    (net (code "38") (name "Net-(R22-Pad1)") (class "Default")
      (node (ref "R22") (pin "1") (pinfunction "1_1") (pintype "passive"))
      (node (ref "T5") (pin "B") (pinfunction "B_B") (pintype "passive"))
    )
    (net (code "39") (name "Net-(R31-Pad2)") (class "Default")
      (node (ref "R31") (pin "2") (pinfunction "2_2") (pintype "passive"))
      (node (ref "T4") (pin "C") (pinfunction "C_C") (pintype "passive"))
    )
    (net (code "40") (name "Net-(STARTB-S)") (class "Default")
      (node (ref "R30") (pin "1") (pinfunction "1_1") (pintype "passive"))
      (node (ref "START") (pin "2") (pinfunction "S_2") (pintype "passive"))
    )
    (net (code "41") (name "Net-(STOPB-S)") (class "Default")
      (node (ref "R31") (pin "1") (pinfunction "1_1") (pintype "passive"))
      (node (ref "STOP") (pin "2") (pinfunction "S_2") (pintype "passive"))
    )
    (net (code "42") (name "Net-(U1A-QC)") (class "Default")
      (node (ref "R21") (pin "1") (pinfunction "1_1") (pintype "passive"))
      (node (ref "U1") (pin "5") (pinfunction "QC_5") (pintype "output"))
    )
    (net (code "43") (name "Net-(U1A-QH)") (class "Default")
      (node (ref "U1") (pin "13") (pinfunction "QH_13") (pintype "output"))
      (node (ref "U2") (pin "1") (pinfunction "A_1") (pintype "input"))
      (node (ref "U2") (pin "2") (pinfunction "B_2") (pintype "input"))
    )
    (net (code "44") (name "Net-(U2A-QE)") (class "Default")
      (node (ref "R22") (pin "2") (pinfunction "2_2") (pintype "passive"))
      (node (ref "U2") (pin "10") (pinfunction "QE_10") (pintype "output"))
    )
    (net (code "45") (name "Net-(U3A-QH)") (class "Default")
      (node (ref "U3") (pin "9") (pinfunction "QH_9") (pintype "output"))
      (node (ref "U4") (pin "5") (pinfunction "I1_5") (pintype "input"))
    )
    (net (code "46") (name "Net-(U4A-I0)") (class "Default")
      (node (ref "U4") (pin "1") (pinfunction "I0_1") (pintype "input"))
      (node (ref "U4") (pin "8") (pinfunction "O_8") (pintype "output"))
    )
    (net (code "47") (name "Net-(U4A-I1)") (class "Default")
      (node (ref "U4") (pin "2") (pinfunction "I1_2") (pintype "input"))
      (node (ref "U4") (pin "6") (pinfunction "O_6") (pintype "output"))
    )
    (net (code "48") (name "Net-(U4B-I0)") (class "Default")
      (node (ref "U4") (pin "11") (pinfunction "O_11") (pintype "output"))
      (node (ref "U4") (pin "4") (pinfunction "I0_4") (pintype "input"))
    )
    (net (code "49") (name "Net-(U5A-I)") (class "Default")
      (node (ref "C3") (pin "2") (pinfunction "2_2") (pintype "passive"))
      (node (ref "R15") (pin "1") (pinfunction "1_1") (pintype "passive"))
      (node (ref "U5") (pin "2") (pinfunction "I_2") (pintype "input"))
    )
    (net (code "50") (name "Net-(U6-AO)") (class "Default")
      (node (ref "R18") (pin "2") (pinfunction "2_2") (pintype "passive"))
      (node (ref "SJ2") (pin "1") (pinfunction "1_1") (pintype "passive"))
      (node (ref "U6") (pin "6") (pinfunction "AO_6") (pintype "bidirectional"))
    )
    (net (code "51") (name "Net-(U6-SCL)") (class "Default")
      (node (ref "R20") (pin "1") (pinfunction "1_1") (pintype "passive"))
      (node (ref "U6") (pin "5") (pinfunction "SCL_5") (pintype "bidirectional"))
      (node (ref "U7") (pin "3") (pinfunction "SCL1_3") (pintype "input"))
    )
    (net (code "52") (name "Net-(U6-SDA)") (class "Default")
      (node (ref "R19") (pin "1") (pinfunction "1_1") (pintype "passive"))
      (node (ref "U6") (pin "4") (pinfunction "SDA_4") (pintype "bidirectional"))
      (node (ref "U7") (pin "2") (pinfunction "SDA1_2") (pintype "input"))
    )
    (net (code "53") (name "ONEWIRE") (class "Default")
      (node (ref "M1") (pin "J6.8") (pinfunction "PC0_J6.8") (pintype "bidirectional"))
      (node (ref "R24") (pin "1") (pinfunction "1_1") (pintype "passive"))
      (node (ref "TEMP") (pin "2") (pinfunction "S_2") (pintype "passive"))
    )
    (net (code "54") (name "RPM_SENSOR") (class "Default")
      (node (ref "M1") (pin "J7.2") (pinfunction "PB0_J7.2") (pintype "bidirectional"))
      (node (ref "U5") (pin "4") (pinfunction "O_4") (pintype "output"))
    )
    (net (code "55") (name "RST") (class "Default")
      (node (ref "ISP") (pin "1") (pinfunction "S_1") (pintype "passive"))
      (node (ref "M1") (pin "J6.3") (pinfunction "RST.1_J6.3") (pintype "bidirectional"))
      (node (ref "M1") (pin "J7.10") (pinfunction "RST.2_J7.10") (pintype "bidirectional"))
    )
    (net (code "56") (name "SCK") (class "Default")
      (node (ref "ISP") (pin "2") (pinfunction "S_2") (pintype "passive"))
      (node (ref "M1") (pin "J6.9") (pinfunction "SCK/PB5_J6.9") (pintype "bidirectional"))
    )
    (net (code "57") (name "SCL") (class "Default")
      (node (ref "DISPLAY") (pin "3") (pinfunction "S_3") (pintype "passive"))
      (node (ref "M1") (pin "J2.2") (pinfunction "SCL/PC5_J2.2") (pintype "bidirectional"))
      (node (ref "R9") (pin "2") (pinfunction "2_2") (pintype "passive"))
      (node (ref "U7") (pin "6") (pinfunction "SCL2_6") (pintype "output"))
    )
    (net (code "58") (name "SDA") (class "Default")
      (node (ref "DISPLAY") (pin "4") (pinfunction "S_4") (pintype "passive"))
      (node (ref "M1") (pin "J2.1") (pinfunction "SDA/PC4_J2.1") (pintype "bidirectional"))
      (node (ref "R10") (pin "2") (pinfunction "2_2") (pintype "passive"))
      (node (ref "U7") (pin "7") (pinfunction "SDA2_7") (pintype "output"))
    )
    (net (code "59") (name "SECURITY_SW") (class "Default")
      (node (ref "C4") (pin "1") (pinfunction "1_1") (pintype "passive"))
      (node (ref "M1") (pin "J7.8") (pinfunction "PD2/INT0_J7.8") (pintype "bidirectional"))
      (node (ref "R17") (pin "1") (pinfunction "1_1") (pintype "passive"))
    )
    (net (code "60") (name "SH{slash}LD_SWITCH") (class "Default")
      (node (ref "J3") (pin "6") (pinfunction "S_6") (pintype "passive"))
      (node (ref "J4") (pin "2") (pinfunction "S_2") (pintype "passive"))
      (node (ref "U3") (pin "1") (pinfunction "SH/~{LD}_1") (pintype "input"))
    )
    (net (code "61") (name "SMC_LED") (class "Default")
      (node (ref "M1") (pin "J7.3") (pinfunction "PD7_J7.3") (pintype "bidirectional"))
      (node (ref "OK1") (pin "4") (pinfunction "COL_4") (pintype "passive"))
    )
    (net (code "62") (name "SMC_SW") (class "Default")
      (node (ref "M1") (pin "J7.4") (pinfunction "PD6/OC0A_J7.4") (pintype "bidirectional"))
      (node (ref "R4") (pin "2") (pinfunction "2_2") (pintype "passive"))
    )
    (net (code "63") (name "STARTLED") (class "Default")
      (node (ref "R30") (pin "2") (pinfunction "2_2") (pintype "passive"))
      (node (ref "T3") (pin "C") (pinfunction "C_C") (pintype "passive"))
    )
    (net (code "64") (name "START_LED_") (class "Default")
      (node (ref "ISP") (pin "4") (pinfunction "S_4") (pintype "passive"))
      (node (ref "M1") (pin "J6.11") (pinfunction "MOSI/PB3_J6.11") (pintype "bidirectional"))
      (node (ref "R2") (pin "2") (pinfunction "2_2") (pintype "passive"))
    )
    (net (code "65") (name "START_SW") (class "Default")
      (node (ref "M1") (pin "J7.6") (pinfunction "PD4_J7.6") (pintype "bidirectional"))
      (node (ref "START") (pin "4") (pinfunction "S_4") (pintype "passive"))
    )
    (net (code "66") (name "STOP_LED_") (class "Default")
      (node (ref "M1") (pin "J6.12") (pinfunction "OC1B/PB2_J6.12") (pintype "bidirectional"))
      (node (ref "R3") (pin "2") (pinfunction "2_2") (pintype "passive"))
    )
    (net (code "67") (name "STOP_SW") (class "Default")
      (node (ref "M1") (pin "J7.7") (pinfunction "PD3/INT1_J7.7") (pintype "bidirectional"))
      (node (ref "STOP") (pin "4") (pinfunction "S_4") (pintype "passive"))
    )
    (net (code "68") (name "VOUT") (class "Default")
      (node (ref "J9") (pin "2") (pinfunction "S_2") (pintype "passive"))
      (node (ref "J9A-") (pin "2") (pinfunction "1_2") (pintype "passive"))
      (node (ref "U6") (pin "1") (pinfunction "VOUT_1") (pintype "bidirectional"))
    )
    (net (code "69") (name "unconnected-(F2-Pad1B)") (class "Default")
      (node (ref "F2") (pin "1B") (pinfunction "1B_1B") (pintype "passive"))
    )
    (net (code "70") (name "unconnected-(F2-Pad2B)") (class "Default")
      (node (ref "F2") (pin "2B") (pinfunction "2B_2B") (pintype "passive"))
    )
    (net (code "71") (name "unconnected-(M1-ADC7-PadJ3.3)") (class "Default")
      (node (ref "M1") (pin "J3.3") (pinfunction "ADC7_J3.3") (pintype "bidirectional"))
    )
    (net (code "72") (name "unconnected-(M1-PD0{slash}RX-PadJ7.11)") (class "Default")
      (node (ref "M1") (pin "J7.11") (pinfunction "PD0/RX_J7.11") (pintype "bidirectional"))
    )
    (net (code "73") (name "unconnected-(M1-PD1{slash}TX-PadJ7.12)") (class "Default")
      (node (ref "M1") (pin "J7.12") (pinfunction "PD1/TX_J7.12") (pintype "bidirectional"))
    )
    (net (code "74") (name "unconnected-(M1-P_CTS-PadJ1.5)") (class "Default")
      (node (ref "M1") (pin "J1.5") (pinfunction "P_CTS_J1.5") (pintype "bidirectional"))
    )
    (net (code "75") (name "unconnected-(M1-P_DTR-PadJ1.1)") (class "Default")
      (node (ref "M1") (pin "J1.1") (pinfunction "P_DTR_J1.1") (pintype "bidirectional"))
    )
    (net (code "76") (name "unconnected-(M1-P_RXD-PadJ1.2)") (class "Default")
      (node (ref "M1") (pin "J1.2") (pinfunction "P_RXD_J1.2") (pintype "bidirectional"))
    )
    (net (code "77") (name "unconnected-(M1-P_TXD-PadJ1.3)") (class "Default")
      (node (ref "M1") (pin "J1.3") (pinfunction "P_TXD_J1.3") (pintype "bidirectional"))
    )
    (net (code "78") (name "unconnected-(U1A-QA-Pad3)") (class "Default")
      (node (ref "U1") (pin "3") (pinfunction "QA_3") (pintype "output"))
    )
    (net (code "79") (name "unconnected-(U1A-QB-Pad4)") (class "Default")
      (node (ref "U1") (pin "4") (pinfunction "QB_4") (pintype "output"))
    )
    (net (code "80") (name "unconnected-(U1A-QD-Pad6)") (class "Default")
      (node (ref "U1") (pin "6") (pinfunction "QD_6") (pintype "output"))
    )
    (net (code "81") (name "unconnected-(U1A-QE-Pad10)") (class "Default")
      (node (ref "U1") (pin "10") (pinfunction "QE_10") (pintype "output"))
    )
    (net (code "82") (name "unconnected-(U1A-QF-Pad11)") (class "Default")
      (node (ref "U1") (pin "11") (pinfunction "QF_11") (pintype "output"))
    )
    (net (code "83") (name "unconnected-(U1A-QG-Pad12)") (class "Default")
      (node (ref "U1") (pin "12") (pinfunction "QG_12") (pintype "output"))
    )
    (net (code "84") (name "unconnected-(U2A-QA-Pad3)") (class "Default")
      (node (ref "U2") (pin "3") (pinfunction "QA_3") (pintype "output"))
    )
    (net (code "85") (name "unconnected-(U2A-QB-Pad4)") (class "Default")
      (node (ref "U2") (pin "4") (pinfunction "QB_4") (pintype "output"))
    )
    (net (code "86") (name "unconnected-(U2A-QC-Pad5)") (class "Default")
      (node (ref "U2") (pin "5") (pinfunction "QC_5") (pintype "output"))
    )
    (net (code "87") (name "unconnected-(U2A-QD-Pad6)") (class "Default")
      (node (ref "U2") (pin "6") (pinfunction "QD_6") (pintype "output"))
    )
    (net (code "88") (name "unconnected-(U2A-QF-Pad11)") (class "Default")
      (node (ref "U2") (pin "11") (pinfunction "QF_11") (pintype "output"))
    )
    (net (code "89") (name "unconnected-(U2A-QG-Pad12)") (class "Default")
      (node (ref "U2") (pin "12") (pinfunction "QG_12") (pintype "output"))
    )
    (net (code "90") (name "unconnected-(U2A-QH-Pad13)") (class "Default")
      (node (ref "U2") (pin "13") (pinfunction "QH_13") (pintype "output"))
    )
    (net (code "91") (name "unconnected-(U3A-~{QH}-Pad7)") (class "Default")
      (node (ref "U3") (pin "7") (pinfunction "~{QH}_7") (pintype "output"))
    )
  )
)
